# BBoard-JX2.net
KiCad netlist of a schematic drawn in Altium Designer
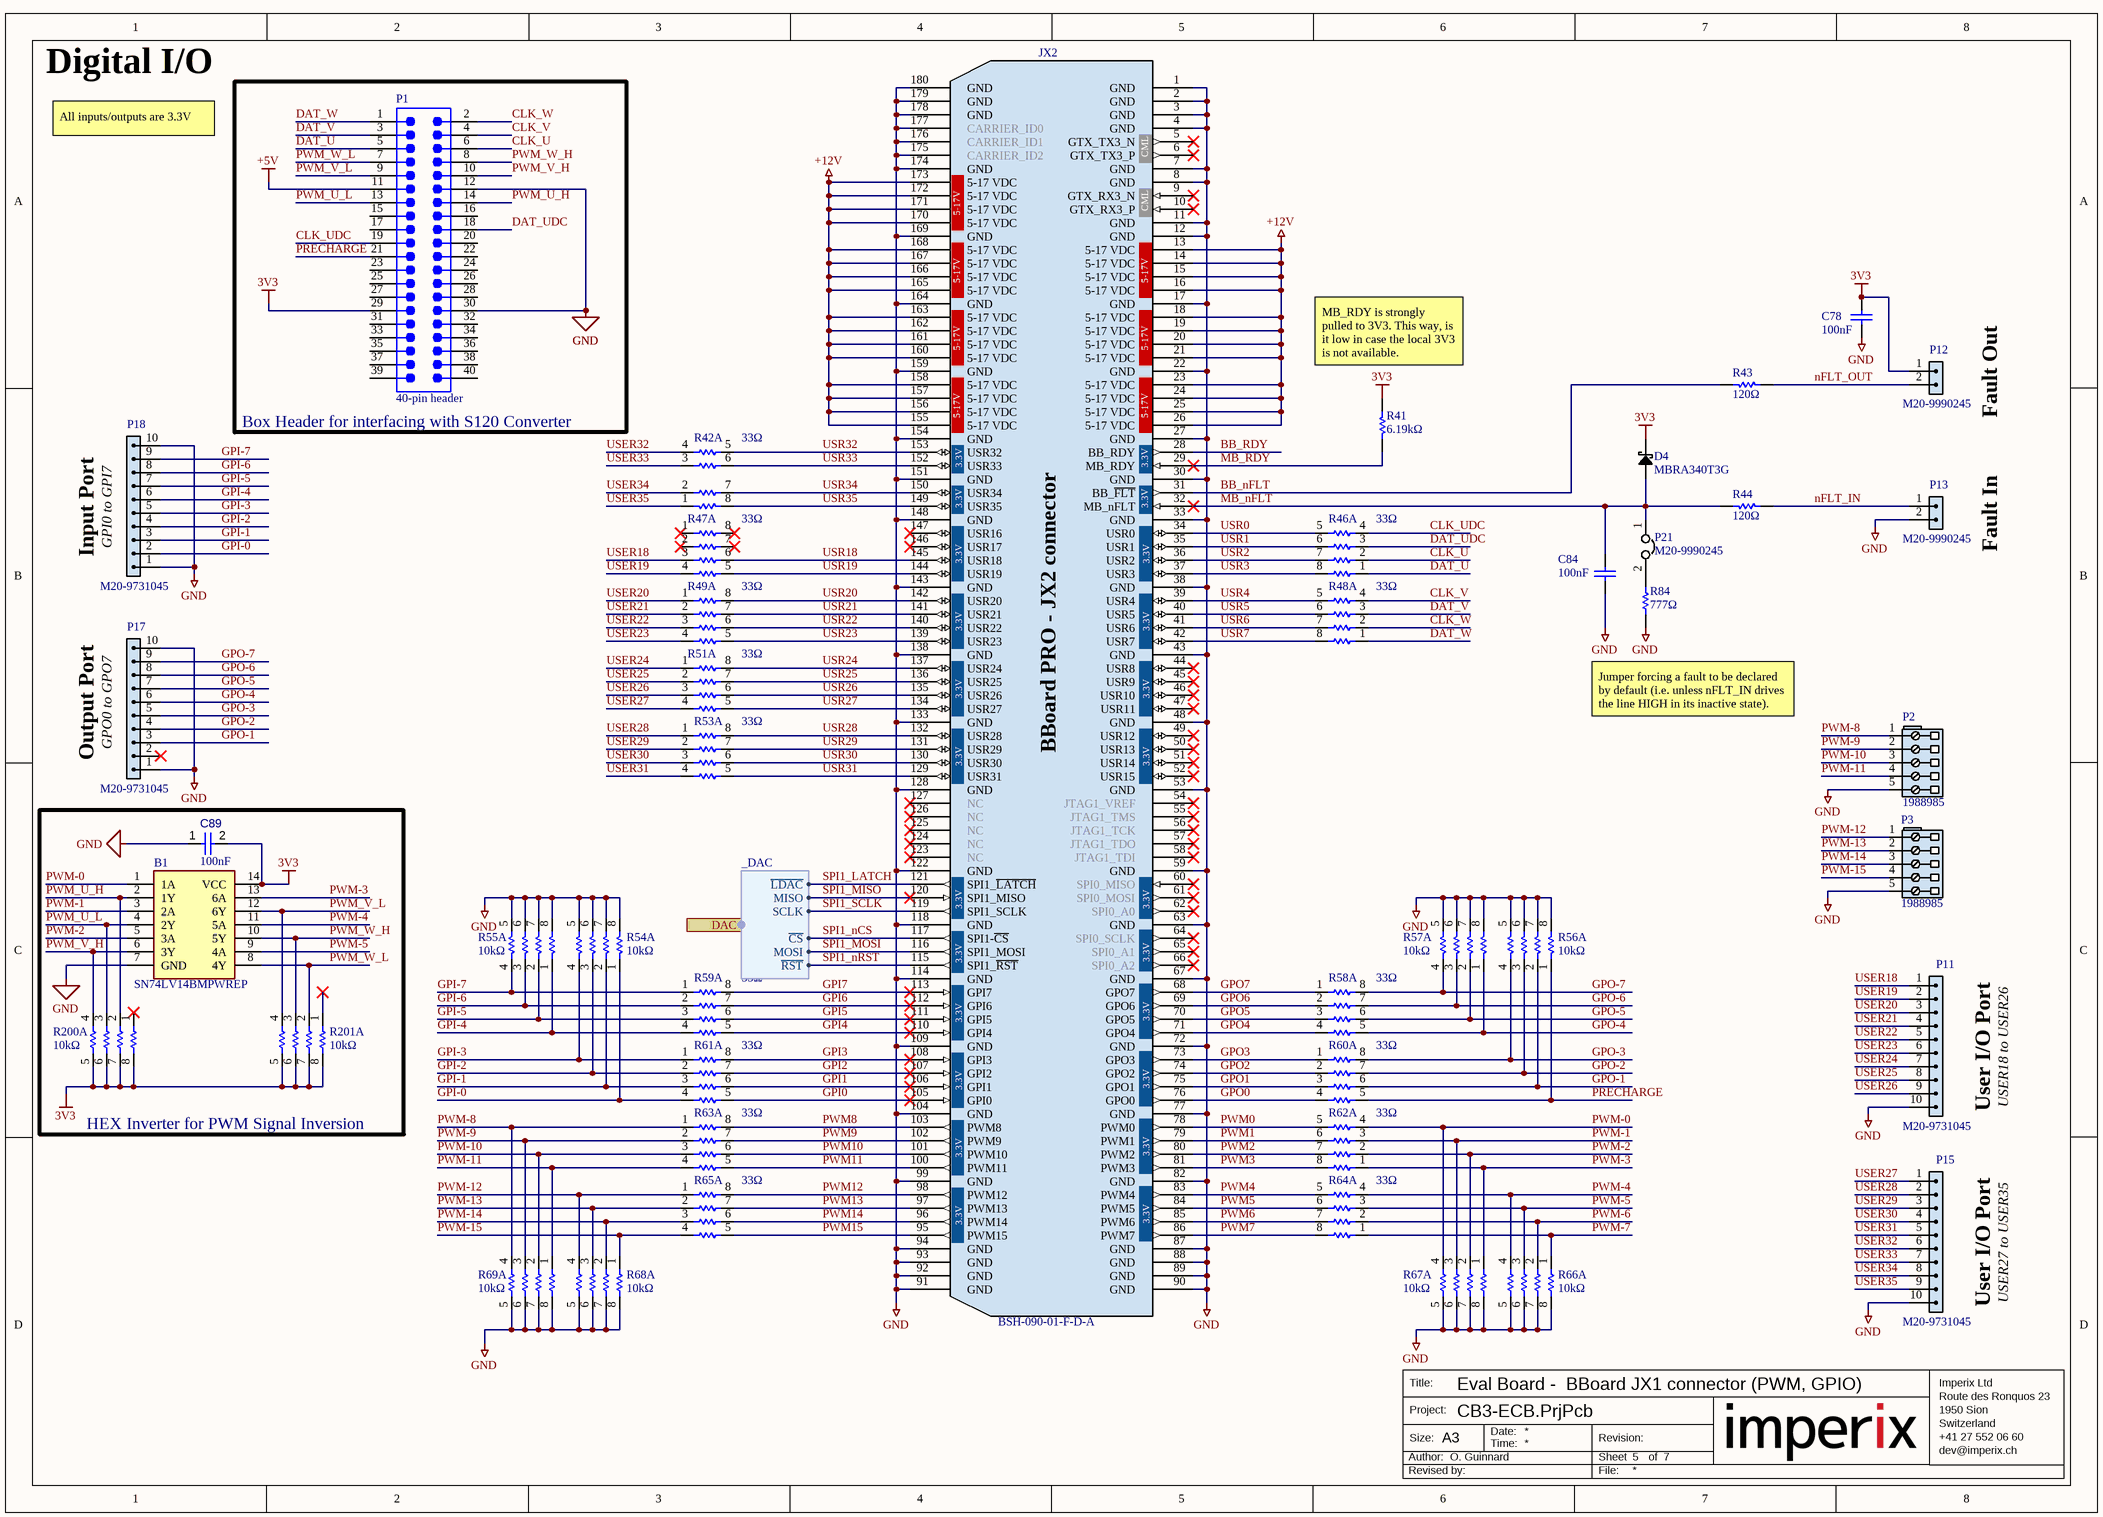
[diagram p0: BBoard-JX2.SchDoc]

(export (version "E")
  (design (tool "Eeschema 10.0.6"))
  (components
    (comp (ref "B1")
      (value "SN74LV14BMPWREP")
      (footprint "SOP65P640X120-14N")
      (fields (field (name "MOUSER PART NUMBER") "595-SN74LV14BMPWREP"))
      (libsource (lib "SN74LV14BMPWREP") (part "SN74LV14BMPWREP"))
    )
    (comp (ref "C78")
      (value "100nF")
      (footprint "CAPC1005L(0402)")
      (description "CAP CER 100NF 25V X7R 0402 10% (Generic Imperix Component)")
      (fields (field (name "TOLERANCE") "10%") (field (name "Comment") "CAP-100NF-25V-X7R-0402-10%"))
      (libsource (lib "CB3-ECB") (part "Capacitor non-polarized"))
    )
    (comp (ref "C84")
      (value "100nF")
      (footprint "CAPC1005L(0402)")
      (description "CAP CER 100NF 25V X7R 0402 10% (Generic Imperix Component)")
      (fields (field (name "TOLERANCE") "10%") (field (name "Comment") "CAP-100NF-25V-X7R-0402-10%"))
      (libsource (lib "CB3-ECB") (part "Capacitor non-polarized"))
    )
    (comp (ref "C89")
      (value "100nF")
      (footprint "CAPC0402(1005)60_L")
      (description "Chip Capacitor, 100nF +/-20%, 50V, 0402, Thickness 0.6 mm")
      (fields (field (name "TOLERANCE") "10%") (field (name "Comment") "Capacitor 100nF +/-20% 50V 0402"))
      (libsource (lib "Technische Universität Darmstadt -  Institut für Stromrichtertechnik und Antriebsregelung") (part "CAP-NP-2"))
    )
    (comp (ref "D4")
      (value "MBRA340T3G")
      (footprint "DO-214AC")
      (description "Diode Schottky 40 V 3A Surface Mount SMA")
      (libsource (lib "CB3-ECB") (part "Diode Schottky"))
    )
    (comp (ref "JX2")
      (value "BSH-090-01-F-D-A")
      (footprint "BSH-090-01-F-D-A")
      (description "JX2 for BBoard")
      (libsource (lib "CB3-ECB") (part "JX2 for Bboard"))
    )
    (comp (ref "P1")
      (value "40-pin header")
      (footprint "61204021621")
      (description "Würth WR-BHD Male Box Header")
      (fields (field (name "MANUFACTURER") "Würth") (field (name "MANUFACTURER PART NUMBER") "61204021621"))
      (libsource (lib "Altium Content Vault") (part "Header_Male_2R_40P"))
    )
    (comp (ref "P2")
      (value "1988985")
      (footprint "1988985")
      (description "Conn PC Terminal Block 5 POS 3.5mm Solder Thru-Hole 17.5A")
      (fields (field (name "VOLTAGE") "300V"))
      (libsource (lib "CB3-ECB") (part "1988985"))
    )
    (comp (ref "P3")
      (value "1988985")
      (footprint "1988985")
      (description "Conn PC Terminal Block 5 POS 3.5mm Solder Thru-Hole 17.5A")
      (fields (field (name "VOLTAGE") "300V"))
      (libsource (lib "CB3-ECB") (part "1988985"))
    )
    (comp (ref "P11")
      (value "M20-9731045")
      (footprint "M20-9731045")
      (description "Connector Header Through Hole 10 position 0.100\" (2.54mm)")
      (libsource (lib "") (part "Header 10-P_1"))
    )
    (comp (ref "P12")
      (value "M20-9990245")
      (footprint "M20-9990245")
      (description "Connector Header Through Hole 2 position 0.100\" (2.54mm)")
      (fields (field (name "VOLTAGE") "50V"))
      (libsource (lib "CB3-ECB") (part "M20-9990245"))
    )
    (comp (ref "P13")
      (value "M20-9990245")
      (footprint "M20-9990245")
      (description "Connector Header Through Hole 2 position 0.100\" (2.54mm)")
      (fields (field (name "VOLTAGE") "50V"))
      (libsource (lib "CB3-ECB") (part "M20-9990245"))
    )
    (comp (ref "P15")
      (value "M20-9731045")
      (footprint "M20-9731045")
      (description "Connector Header Through Hole 10 position 0.100\" (2.54mm)")
      (libsource (lib "") (part "Header 10-P_1"))
    )
    (comp (ref "P17")
      (value "M20-9731045")
      (footprint "M20-9731045")
      (description "Connector Header Through Hole 10 position 0.100\" (2.54mm)")
      (libsource (lib "CB3-ECB") (part "Header 10-P"))
    )
    (comp (ref "P18")
      (value "M20-9731045")
      (footprint "M20-9731045")
      (description "Connector Header Through Hole 10 position 0.100\" (2.54mm)")
      (libsource (lib "CB3-ECB") (part "Header 10-P"))
    )
    (comp (ref "P21")
      (value "M20-9990245")
      (footprint "M20-9990245")
      (description "Connector Header Through Hole 2 position 0.100\" (2.54mm)")
      (fields (field (name "VOLTAGE") "50V"))
      (libsource (lib "CB3-ECB") (part "Jumper 2-P"))
    )
    (comp (ref "R41")
      (value "6.19kΩ")
      (footprint "RESC1005L(0402)")
      (description "RES SMD 6.19KΩ 1/16W 100PPM 0402 1% (Generic Imperix Component)")
      (fields (field (name "TOLERANCE") "1%") (field (name "Comment") "RES-6.19KΩ-1/16W-100PPM-0402-1%"))
      (libsource (lib "CB3-ECB") (part "Resistor"))
    )
    (comp (ref "R42")
      (value "33Ω")
      (footprint "RESQUAD0804")
      (description "Res Thick Film Array 33 Ohm 5% ±200ppm/°C ISOL 8-Pin 0804(4 X 0402) Convex SMD Automotive T/R")
      (fields (field (name "TOLERANCE") "5%") (field (name "Comment") "EXB-28V330JX"))
      (libsource (lib "CB3-ECB") (part "Resistor Array Quad"))
    )
    (comp (ref "R43")
      (value "120Ω")
      (footprint "RESC1005L(0402)")
      (description "RES SMD 120Ω 1/16W 25PPM 0402 0.1% (Generic Imperix Component)")
      (fields (field (name "TOLERANCE") "0.1%") (field (name "Comment") "RES-120Ω-1/16W-25PPM-0402-0.1%"))
      (libsource (lib "CB3-ECB") (part "Resistor"))
    )
    (comp (ref "R44")
      (value "120Ω")
      (footprint "RESC1005L(0402)")
      (description "RES SMD 120Ω 1/16W 25PPM 0402 0.1% (Generic Imperix Component)")
      (fields (field (name "TOLERANCE") "0.1%") (field (name "Comment") "RES-120Ω-1/16W-25PPM-0402-0.1%"))
      (libsource (lib "CB3-ECB") (part "Resistor"))
    )
    (comp (ref "R46")
      (value "33Ω")
      (footprint "RESQUAD0804")
      (description "Res Thick Film Array 33 Ohm 5% ±200ppm/°C ISOL 8-Pin 0804(4 X 0402) Convex SMD Automotive T/R")
      (fields (field (name "TOLERANCE") "5%") (field (name "Comment") "EXB-28V330JX"))
      (libsource (lib "CB3-ECB") (part "Resistor Array Quad"))
    )
    (comp (ref "R47")
      (value "33Ω")
      (footprint "RESQUAD0804")
      (description "Res Thick Film Array 33 Ohm 5% ±200ppm/°C ISOL 8-Pin 0804(4 X 0402) Convex SMD Automotive T/R")
      (fields (field (name "TOLERANCE") "5%") (field (name "Comment") "EXB-28V330JX"))
      (libsource (lib "CB3-ECB") (part "Resistor Array Quad"))
    )
    (comp (ref "R48")
      (value "33Ω")
      (footprint "RESQUAD0804")
      (description "Res Thick Film Array 33 Ohm 5% ±200ppm/°C ISOL 8-Pin 0804(4 X 0402) Convex SMD Automotive T/R")
      (fields (field (name "TOLERANCE") "5%") (field (name "Comment") "EXB-28V330JX"))
      (libsource (lib "CB3-ECB") (part "Resistor Array Quad"))
    )
    (comp (ref "R49")
      (value "33Ω")
      (footprint "RESQUAD0804")
      (description "Res Thick Film Array 33 Ohm 5% ±200ppm/°C ISOL 8-Pin 0804(4 X 0402) Convex SMD Automotive T/R")
      (fields (field (name "TOLERANCE") "5%") (field (name "Comment") "EXB-28V330JX"))
      (libsource (lib "CB3-ECB") (part "Resistor Array Quad"))
    )
    (comp (ref "R51")
      (value "33Ω")
      (footprint "RESQUAD0804")
      (description "Res Thick Film Array 33 Ohm 5% ±200ppm/°C ISOL 8-Pin 0804(4 X 0402) Convex SMD Automotive T/R")
      (fields (field (name "TOLERANCE") "5%") (field (name "Comment") "EXB-28V330JX"))
      (libsource (lib "CB3-ECB") (part "Resistor Array Quad"))
    )
    (comp (ref "R53")
      (value "33Ω")
      (footprint "RESQUAD0804")
      (description "Res Thick Film Array 33 Ohm 5% ±200ppm/°C ISOL 8-Pin 0804(4 X 0402) Convex SMD Automotive T/R")
      (fields (field (name "TOLERANCE") "5%") (field (name "Comment") "EXB-28V330JX"))
      (libsource (lib "CB3-ECB") (part "Resistor Array Quad"))
    )
    (comp (ref "R54")
      (value "EXB-28V103JX")
      (footprint "RESQUAD0804")
      (description "Res Thick Film Array 10KΩ 5% ±200ppm/°C ISOL 8-Pin 0804(4 X 0402) Convex SMD Automotive T/R")
      (fields (field (name "TOLERANCE") "5%") (field (name "Comment") "EXB-28V103JX"))
      (libsource (lib "CB3-ECB") (part "Resistor Array Quad"))
    )
    (comp (ref "R55")
      (value "10kΩ")
      (footprint "RESQUAD0804")
      (description "Res Thick Film Array 10KΩ 5% ±200ppm/°C ISOL 8-Pin 0804(4 X 0402) Convex SMD Automotive T/R")
      (fields (field (name "TOLERANCE") "5%") (field (name "Comment") "EXB-28V103JX"))
      (libsource (lib "CB3-ECB") (part "Resistor Array Quad"))
    )
    (comp (ref "R56")
      (value "10kΩ")
      (footprint "RESQUAD0804")
      (description "Res Thick Film Array 10KΩ 5% ±200ppm/°C ISOL 8-Pin 0804(4 X 0402) Convex SMD Automotive T/R")
      (fields (field (name "TOLERANCE") "5%") (field (name "Comment") "EXB-28V103JX"))
      (libsource (lib "CB3-ECB") (part "Resistor Array Quad"))
    )
    (comp (ref "R57")
      (value "10kΩ")
      (footprint "RESQUAD0804")
      (description "Res Thick Film Array 10KΩ 5% ±200ppm/°C ISOL 8-Pin 0804(4 X 0402) Convex SMD Automotive T/R")
      (fields (field (name "TOLERANCE") "5%") (field (name "Comment") "EXB-28V103JX"))
      (libsource (lib "CB3-ECB") (part "Resistor Array Quad"))
    )
    (comp (ref "R58")
      (value "33Ω")
      (footprint "RESQUAD0804")
      (description "Res Thick Film Array 33 Ohm 5% ±200ppm/°C ISOL 8-Pin 0804(4 X 0402) Convex SMD Automotive T/R")
      (fields (field (name "TOLERANCE") "5%") (field (name "Comment") "EXB-28V330JX"))
      (libsource (lib "CB3-ECB") (part "Resistor Array Quad"))
    )
    (comp (ref "R59")
      (value "EXB-28V330JX")
      (footprint "RESQUAD0804")
      (description "Res Thick Film Array 33 Ohm 5% ±200ppm/°C ISOL 8-Pin 0804(4 X 0402) Convex SMD Automotive T/R")
      (fields (field (name "TOLERANCE") "5%") (field (name "Comment") "EXB-28V330JX"))
      (libsource (lib "CB3-ECB") (part "Resistor Array Quad"))
    )
    (comp (ref "R60")
      (value "33Ω")
      (footprint "RESQUAD0804")
      (description "Res Thick Film Array 33 Ohm 5% ±200ppm/°C ISOL 8-Pin 0804(4 X 0402) Convex SMD Automotive T/R")
      (fields (field (name "TOLERANCE") "5%") (field (name "Comment") "EXB-28V330JX"))
      (libsource (lib "CB3-ECB") (part "Resistor Array Quad"))
    )
    (comp (ref "R61")
      (value "EXB-28V330JX")
      (footprint "RESQUAD0804")
      (description "Res Thick Film Array 33 Ohm 5% ±200ppm/°C ISOL 8-Pin 0804(4 X 0402) Convex SMD Automotive T/R")
      (fields (field (name "TOLERANCE") "5%") (field (name "Comment") "EXB-28V330JX"))
      (libsource (lib "CB3-ECB") (part "Resistor Array Quad"))
    )
    (comp (ref "R62")
      (value "33Ω")
      (footprint "RESQUAD0804")
      (description "Res Thick Film Array 33 Ohm 5% ±200ppm/°C ISOL 8-Pin 0804(4 X 0402) Convex SMD Automotive T/R")
      (fields (field (name "TOLERANCE") "5%") (field (name "Comment") "EXB-28V330JX"))
      (libsource (lib "CB3-ECB") (part "Resistor Array Quad"))
    )
    (comp (ref "R63")
      (value "33Ω")
      (footprint "RESQUAD0804")
      (description "Res Thick Film Array 33 Ohm 5% ±200ppm/°C ISOL 8-Pin 0804(4 X 0402) Convex SMD Automotive T/R")
      (fields (field (name "TOLERANCE") "5%") (field (name "Comment") "EXB-28V330JX"))
      (libsource (lib "CB3-ECB") (part "Resistor Array Quad"))
    )
    (comp (ref "R64")
      (value "EXB-28V330JX")
      (footprint "RESQUAD0804")
      (description "Res Thick Film Array 33 Ohm 5% ±200ppm/°C ISOL 8-Pin 0804(4 X 0402) Convex SMD Automotive T/R")
      (fields (field (name "TOLERANCE") "5%") (field (name "Comment") "EXB-28V330JX"))
      (libsource (lib "CB3-ECB") (part "Resistor Array Quad"))
    )
    (comp (ref "R65")
      (value "EXB-28V330JX")
      (footprint "RESQUAD0804")
      (description "Res Thick Film Array 33 Ohm 5% ±200ppm/°C ISOL 8-Pin 0804(4 X 0402) Convex SMD Automotive T/R")
      (fields (field (name "TOLERANCE") "5%") (field (name "Comment") "EXB-28V330JX"))
      (libsource (lib "CB3-ECB") (part "Resistor Array Quad"))
    )
    (comp (ref "R66")
      (value "10kΩ")
      (footprint "RESQUAD0804")
      (description "Res Thick Film Array 10KΩ 5% ±200ppm/°C ISOL 8-Pin 0804(4 X 0402) Convex SMD Automotive T/R")
      (fields (field (name "TOLERANCE") "5%") (field (name "Comment") "EXB-28V103JX"))
      (libsource (lib "CB3-ECB") (part "Resistor Array Quad"))
    )
    (comp (ref "R67")
      (value "10kΩ")
      (footprint "RESQUAD0804")
      (description "Res Thick Film Array 10KΩ 5% ±200ppm/°C ISOL 8-Pin 0804(4 X 0402) Convex SMD Automotive T/R")
      (fields (field (name "TOLERANCE") "5%") (field (name "Comment") "EXB-28V103JX"))
      (libsource (lib "CB3-ECB") (part "Resistor Array Quad"))
    )
    (comp (ref "R68")
      (value "EXB-28V103JX")
      (footprint "RESQUAD0804")
      (description "Res Thick Film Array 10KΩ 5% ±200ppm/°C ISOL 8-Pin 0804(4 X 0402) Convex SMD Automotive T/R")
      (fields (field (name "TOLERANCE") "5%") (field (name "Comment") "EXB-28V103JX"))
      (libsource (lib "CB3-ECB") (part "Resistor Array Quad"))
    )
    (comp (ref "R69")
      (value "10kΩ")
      (footprint "RESQUAD0804")
      (description "Res Thick Film Array 10KΩ 5% ±200ppm/°C ISOL 8-Pin 0804(4 X 0402) Convex SMD Automotive T/R")
      (fields (field (name "TOLERANCE") "5%") (field (name "Comment") "EXB-28V103JX"))
      (libsource (lib "CB3-ECB") (part "Resistor Array Quad"))
    )
    (comp (ref "R84")
      (value "777Ω")
      (footprint "RESC1005L(0402)")
      (description "RES SMD 777Ω 1/16W 25PPM 0402 0.1% (Generic Imperix Component)")
      (fields (field (name "TOLERANCE") "0.1%") (field (name "Comment") "RES-777Ω-1/16W-25PPM-0402-0.1%"))
      (libsource (lib "CB3-ECB") (part "Resistor"))
    )
    (comp (ref "R200")
      (value "10kΩ")
      (footprint "RESQUAD0804")
      (description "Res Thick Film Array 10KΩ 5% ±200ppm/°C ISOL 8-Pin 0804(4 X 0402) Convex SMD Automotive T/R")
      (fields (field (name "TOLERANCE") "5%") (field (name "Comment") "EXB-28V103JX"))
      (libsource (lib "CB3-ECB") (part "Resistor Array Quad"))
    )
    (comp (ref "R201")
      (value "10kΩ")
      (footprint "RESQUAD0804")
      (description "Res Thick Film Array 10KΩ 5% ±200ppm/°C ISOL 8-Pin 0804(4 X 0402) Convex SMD Automotive T/R")
      (fields (field (name "TOLERANCE") "5%") (field (name "Comment") "EXB-28V103JX"))
      (libsource (lib "CB3-ECB") (part "Resistor Array Quad"))
    )
  )
  (nets
    (net (code "2") (name "+5V") (class "Default")
      (node (ref "P1") (pin "11") (pinfunction "11_11") (pintype "passive"))
    )
    (net (code "3") (name "+12V") (class "Default")
      (node (ref "JX2") (pin "13") (pinfunction "5-17_VDC_13") (pintype "power_in"))
      (node (ref "JX2") (pin "14") (pinfunction "5-17_VDC_14") (pintype "power_in"))
      (node (ref "JX2") (pin "15") (pinfunction "5-17_VDC_15") (pintype "power_in"))
      (node (ref "JX2") (pin "155") (pinfunction "5-17_VDC_155") (pintype "power_in"))
      (node (ref "JX2") (pin "156") (pinfunction "5-17_VDC_156") (pintype "power_in"))
      (node (ref "JX2") (pin "157") (pinfunction "5-17_VDC_157") (pintype "power_in"))
      (node (ref "JX2") (pin "158") (pinfunction "5-17_VDC_158") (pintype "power_in"))
      (node (ref "JX2") (pin "16") (pinfunction "5-17_VDC_16") (pintype "power_in"))
      (node (ref "JX2") (pin "160") (pinfunction "5-17_VDC_160") (pintype "power_in"))
      (node (ref "JX2") (pin "161") (pinfunction "5-17_VDC_161") (pintype "power_in"))
      (node (ref "JX2") (pin "162") (pinfunction "5-17_VDC_162") (pintype "power_in"))
      (node (ref "JX2") (pin "163") (pinfunction "5-17_VDC_163") (pintype "power_in"))
      (node (ref "JX2") (pin "165") (pinfunction "5-17_VDC_165") (pintype "power_in"))
      (node (ref "JX2") (pin "166") (pinfunction "5-17_VDC_166") (pintype "power_in"))
      (node (ref "JX2") (pin "167") (pinfunction "5-17_VDC_167") (pintype "power_in"))
      (node (ref "JX2") (pin "168") (pinfunction "5-17_VDC_168") (pintype "power_in"))
      (node (ref "JX2") (pin "170") (pinfunction "5-17_VDC_170") (pintype "power_in"))
      (node (ref "JX2") (pin "171") (pinfunction "5-17_VDC_171") (pintype "power_in"))
      (node (ref "JX2") (pin "172") (pinfunction "5-17_VDC_172") (pintype "power_in"))
      (node (ref "JX2") (pin "173") (pinfunction "5-17_VDC_173") (pintype "power_in"))
      (node (ref "JX2") (pin "18") (pinfunction "5-17_VDC_18") (pintype "power_in"))
      (node (ref "JX2") (pin "19") (pinfunction "5-17_VDC_19") (pintype "power_in"))
      (node (ref "JX2") (pin "20") (pinfunction "5-17_VDC_20") (pintype "power_in"))
      (node (ref "JX2") (pin "21") (pinfunction "5-17_VDC_21") (pintype "power_in"))
      (node (ref "JX2") (pin "23") (pinfunction "5-17_VDC_23") (pintype "power_in"))
      (node (ref "JX2") (pin "24") (pinfunction "5-17_VDC_24") (pintype "power_in"))
      (node (ref "JX2") (pin "25") (pinfunction "5-17_VDC_25") (pintype "power_in"))
      (node (ref "JX2") (pin "26") (pinfunction "5-17_VDC_26") (pintype "power_in"))
    )
    (net (code "4") (name "/BB_RDY") (class "Default")
      (node (ref "JX2") (pin "28") (pinfunction "BB_RDY_28") (pintype "output"))
    )
    (net (code "5") (name "/BB_nFLT") (class "Default")
      (node (ref "JX2") (pin "31") (pinfunction "BB_~{FLT}_31") (pintype "output"))
      (node (ref "R43") (pin "1") (pinfunction "1_1") (pintype "passive"))
    )
    (net (code "6") (name "/CLK_U") (class "Default")
      (node (ref "P1") (pin "6") (pinfunction "6_6") (pintype "passive"))
      (node (ref "R46") (pin "2") (pinfunction "2_2") (pintype "passive"))
    )
    (net (code "7") (name "/CLK_UDC") (class "Default")
      (node (ref "P1") (pin "19") (pinfunction "19_19") (pintype "passive"))
      (node (ref "R46") (pin "4") (pinfunction "4_4") (pintype "passive"))
    )
    (net (code "8") (name "/CLK_V") (class "Default")
      (node (ref "P1") (pin "4") (pinfunction "4_4") (pintype "passive"))
      (node (ref "R48") (pin "4") (pinfunction "4_4") (pintype "passive"))
    )
    (net (code "9") (name "/CLK_W") (class "Default")
      (node (ref "P1") (pin "2") (pinfunction "2_2") (pintype "passive"))
      (node (ref "R48") (pin "2") (pinfunction "2_2") (pintype "passive"))
    )
    (net (code "10") (name "/DAT_U") (class "Default")
      (node (ref "P1") (pin "5") (pinfunction "5_5") (pintype "passive"))
      (node (ref "R46") (pin "1") (pinfunction "1_1") (pintype "passive"))
    )
    (net (code "11") (name "/DAT_UDC") (class "Default")
      (node (ref "P1") (pin "18") (pinfunction "18_18") (pintype "passive"))
      (node (ref "R46") (pin "3") (pinfunction "3_3") (pintype "passive"))
    )
    (net (code "12") (name "/DAT_V") (class "Default")
      (node (ref "P1") (pin "3") (pinfunction "3_3") (pintype "passive"))
      (node (ref "R48") (pin "3") (pinfunction "3_3") (pintype "passive"))
    )
    (net (code "13") (name "/DAT_W") (class "Default")
      (node (ref "P1") (pin "1") (pinfunction "1_1") (pintype "passive"))
      (node (ref "R48") (pin "1") (pinfunction "1_1") (pintype "passive"))
    )
    (net (code "14") (name "/GPI-0") (class "Default")
      (node (ref "P18") (pin "2") (pinfunction "2_2") (pintype "passive"))
      (node (ref "R54") (pin "1") (pinfunction "1_1") (pintype "passive"))
      (node (ref "R61") (pin "4") (pinfunction "4_4") (pintype "passive"))
    )
    (net (code "15") (name "/GPI-1") (class "Default")
      (node (ref "P18") (pin "3") (pinfunction "3_3") (pintype "passive"))
      (node (ref "R54") (pin "2") (pinfunction "2_2") (pintype "passive"))
      (node (ref "R61") (pin "3") (pinfunction "3_3") (pintype "passive"))
    )
    (net (code "16") (name "/GPI-2") (class "Default")
      (node (ref "P18") (pin "4") (pinfunction "4_4") (pintype "passive"))
      (node (ref "R54") (pin "3") (pinfunction "3_3") (pintype "passive"))
      (node (ref "R61") (pin "2") (pinfunction "2_2") (pintype "passive"))
    )
    (net (code "17") (name "/GPI-3") (class "Default")
      (node (ref "P18") (pin "5") (pinfunction "5_5") (pintype "passive"))
      (node (ref "R54") (pin "4") (pinfunction "4_4") (pintype "passive"))
      (node (ref "R61") (pin "1") (pinfunction "1_1") (pintype "passive"))
    )
    (net (code "18") (name "/GPI-4") (class "Default")
      (node (ref "P18") (pin "6") (pinfunction "6_6") (pintype "passive"))
      (node (ref "R55") (pin "1") (pinfunction "1_1") (pintype "passive"))
      (node (ref "R59") (pin "4") (pinfunction "4_4") (pintype "passive"))
    )
    (net (code "19") (name "/GPI-5") (class "Default")
      (node (ref "P18") (pin "7") (pinfunction "7_7") (pintype "passive"))
      (node (ref "R55") (pin "2") (pinfunction "2_2") (pintype "passive"))
      (node (ref "R59") (pin "3") (pinfunction "3_3") (pintype "passive"))
    )
    (net (code "20") (name "/GPI-6") (class "Default")
      (node (ref "P18") (pin "8") (pinfunction "8_8") (pintype "passive"))
      (node (ref "R55") (pin "3") (pinfunction "3_3") (pintype "passive"))
      (node (ref "R59") (pin "2") (pinfunction "2_2") (pintype "passive"))
    )
    (net (code "21") (name "/GPI-7") (class "Default")
      (node (ref "P18") (pin "9") (pinfunction "9_9") (pintype "passive"))
      (node (ref "R55") (pin "4") (pinfunction "4_4") (pintype "passive"))
      (node (ref "R59") (pin "1") (pinfunction "1_1") (pintype "passive"))
    )
    (net (code "22") (name "/GPI0") (class "Default")
      (node (ref "JX2") (pin "105") (pinfunction "GPI0_105") (pintype "input"))
      (node (ref "R61") (pin "5") (pinfunction "5_5") (pintype "passive"))
    )
    (net (code "23") (name "/GPI1") (class "Default")
      (node (ref "JX2") (pin "106") (pinfunction "GPI1_106") (pintype "input"))
      (node (ref "R61") (pin "6") (pinfunction "6_6") (pintype "passive"))
    )
    (net (code "24") (name "/GPI2") (class "Default")
      (node (ref "JX2") (pin "107") (pinfunction "GPI2_107") (pintype "input"))
      (node (ref "R61") (pin "7") (pinfunction "7_7") (pintype "passive"))
    )
    (net (code "25") (name "/GPI3") (class "Default")
      (node (ref "JX2") (pin "108") (pinfunction "GPI3_108") (pintype "input"))
      (node (ref "R61") (pin "8") (pinfunction "8_8") (pintype "passive"))
    )
    (net (code "26") (name "/GPI4") (class "Default")
      (node (ref "JX2") (pin "110") (pinfunction "GPI4_110") (pintype "input"))
      (node (ref "R59") (pin "5") (pinfunction "5_5") (pintype "passive"))
    )
    (net (code "27") (name "/GPI5") (class "Default")
      (node (ref "JX2") (pin "111") (pinfunction "GPI5_111") (pintype "input"))
      (node (ref "R59") (pin "6") (pinfunction "6_6") (pintype "passive"))
    )
    (net (code "28") (name "/GPI6") (class "Default")
      (node (ref "JX2") (pin "112") (pinfunction "GPI6_112") (pintype "input"))
      (node (ref "R59") (pin "7") (pinfunction "7_7") (pintype "passive"))
    )
    (net (code "29") (name "/GPI7") (class "Default")
      (node (ref "JX2") (pin "113") (pinfunction "GPI7_113") (pintype "input"))
      (node (ref "R59") (pin "8") (pinfunction "8_8") (pintype "passive"))
    )
    (net (code "30") (name "/GPO-1") (class "Default")
      (node (ref "P17") (pin "3") (pinfunction "3_3") (pintype "passive"))
      (node (ref "R56") (pin "2") (pinfunction "2_2") (pintype "passive"))
      (node (ref "R60") (pin "6") (pinfunction "6_6") (pintype "passive"))
    )
    (net (code "31") (name "/GPO-2") (class "Default")
      (node (ref "P17") (pin "4") (pinfunction "4_4") (pintype "passive"))
      (node (ref "R56") (pin "3") (pinfunction "3_3") (pintype "passive"))
      (node (ref "R60") (pin "7") (pinfunction "7_7") (pintype "passive"))
    )
    (net (code "32") (name "/GPO-3") (class "Default")
      (node (ref "P17") (pin "5") (pinfunction "5_5") (pintype "passive"))
      (node (ref "R56") (pin "4") (pinfunction "4_4") (pintype "passive"))
      (node (ref "R60") (pin "8") (pinfunction "8_8") (pintype "passive"))
    )
    (net (code "33") (name "/GPO-4") (class "Default")
      (node (ref "P17") (pin "6") (pinfunction "6_6") (pintype "passive"))
      (node (ref "R57") (pin "1") (pinfunction "1_1") (pintype "passive"))
      (node (ref "R58") (pin "5") (pinfunction "5_5") (pintype "passive"))
    )
    (net (code "34") (name "/GPO-5") (class "Default")
      (node (ref "P17") (pin "7") (pinfunction "7_7") (pintype "passive"))
      (node (ref "R57") (pin "2") (pinfunction "2_2") (pintype "passive"))
      (node (ref "R58") (pin "6") (pinfunction "6_6") (pintype "passive"))
    )
    (net (code "35") (name "/GPO-6") (class "Default")
      (node (ref "P17") (pin "8") (pinfunction "8_8") (pintype "passive"))
      (node (ref "R57") (pin "3") (pinfunction "3_3") (pintype "passive"))
      (node (ref "R58") (pin "7") (pinfunction "7_7") (pintype "passive"))
    )
    (net (code "36") (name "/GPO-7") (class "Default")
      (node (ref "P17") (pin "9") (pinfunction "9_9") (pintype "passive"))
      (node (ref "R57") (pin "4") (pinfunction "4_4") (pintype "passive"))
      (node (ref "R58") (pin "8") (pinfunction "8_8") (pintype "passive"))
    )
    (net (code "37") (name "/GPO0") (class "Default")
      (node (ref "JX2") (pin "76") (pinfunction "GPO0_76") (pintype "output"))
      (node (ref "R60") (pin "4") (pinfunction "4_4") (pintype "passive"))
    )
    (net (code "38") (name "/GPO1") (class "Default")
      (node (ref "JX2") (pin "75") (pinfunction "GPO1_75") (pintype "output"))
      (node (ref "R60") (pin "3") (pinfunction "3_3") (pintype "passive"))
    )
    (net (code "39") (name "/GPO2") (class "Default")
      (node (ref "JX2") (pin "74") (pinfunction "GPO2_74") (pintype "output"))
      (node (ref "R60") (pin "2") (pinfunction "2_2") (pintype "passive"))
    )
    (net (code "40") (name "/GPO3") (class "Default")
      (node (ref "JX2") (pin "73") (pinfunction "GPO3_73") (pintype "output"))
      (node (ref "R60") (pin "1") (pinfunction "1_1") (pintype "passive"))
    )
    (net (code "41") (name "/GPO4") (class "Default")
      (node (ref "JX2") (pin "71") (pinfunction "GPO4_71") (pintype "output"))
      (node (ref "R58") (pin "4") (pinfunction "4_4") (pintype "passive"))
    )
    (net (code "42") (name "/GPO5") (class "Default")
      (node (ref "JX2") (pin "70") (pinfunction "GPO5_70") (pintype "output"))
      (node (ref "R58") (pin "3") (pinfunction "3_3") (pintype "passive"))
    )
    (net (code "43") (name "/GPO6") (class "Default")
      (node (ref "JX2") (pin "69") (pinfunction "GPO6_69") (pintype "output"))
      (node (ref "R58") (pin "2") (pinfunction "2_2") (pintype "passive"))
    )
    (net (code "44") (name "/GPO7") (class "Default")
      (node (ref "JX2") (pin "68") (pinfunction "GPO7_68") (pintype "output"))
      (node (ref "R58") (pin "1") (pinfunction "1_1") (pintype "passive"))
    )
    (net (code "45") (name "/MB_RDY") (class "Default")
      (node (ref "JX2") (pin "29") (pinfunction "MB_RDY_29") (pintype "input"))
      (node (ref "R41") (pin "2") (pinfunction "2_2") (pintype "passive"))
    )
    (net (code "46") (name "/MB_nFLT") (class "Default")
      (node (ref "C84") (pin "2") (pinfunction "2_2") (pintype "passive"))
      (node (ref "D4") (pin "A") (pinfunction "A_A") (pintype "passive"))
      (node (ref "JX2") (pin "32") (pinfunction "MB_nFLT_32") (pintype "input"))
      (node (ref "P21") (pin "1") (pinfunction "1_1") (pintype "passive"))
      (node (ref "R44") (pin "1") (pinfunction "1_1") (pintype "passive"))
    )
    (net (code "47") (name "/PRECHARGE") (class "Default")
      (node (ref "P1") (pin "21") (pinfunction "21_21") (pintype "passive"))
      (node (ref "R56") (pin "1") (pinfunction "1_1") (pintype "passive"))
      (node (ref "R60") (pin "5") (pinfunction "5_5") (pintype "passive"))
    )
    (net (code "48") (name "/PWM-0") (class "Default")
      (node (ref "B1") (pin "1") (pinfunction "1A_1") (pintype "passive"))
      (node (ref "R62") (pin "4") (pinfunction "4_4") (pintype "passive"))
      (node (ref "R67") (pin "4") (pinfunction "4_4") (pintype "passive"))
    )
    (net (code "49") (name "/PWM-1") (class "Default")
      (node (ref "B1") (pin "3") (pinfunction "2A_3") (pintype "passive"))
      (node (ref "R62") (pin "3") (pinfunction "3_3") (pintype "passive"))
      (node (ref "R67") (pin "3") (pinfunction "3_3") (pintype "passive"))
    )
    (net (code "50") (name "/PWM-2") (class "Default")
      (node (ref "B1") (pin "5") (pinfunction "3A_5") (pintype "passive"))
      (node (ref "R62") (pin "2") (pinfunction "2_2") (pintype "passive"))
      (node (ref "R67") (pin "2") (pinfunction "2_2") (pintype "passive"))
    )
    (net (code "51") (name "/PWM-3") (class "Default")
      (node (ref "B1") (pin "13") (pinfunction "6A_13") (pintype "passive"))
      (node (ref "R62") (pin "1") (pinfunction "1_1") (pintype "passive"))
      (node (ref "R67") (pin "1") (pinfunction "1_1") (pintype "passive"))
    )
    (net (code "52") (name "/PWM-4") (class "Default")
      (node (ref "B1") (pin "11") (pinfunction "5A_11") (pintype "passive"))
      (node (ref "R64") (pin "4") (pinfunction "4_4") (pintype "passive"))
      (node (ref "R66") (pin "4") (pinfunction "4_4") (pintype "passive"))
    )
    (net (code "53") (name "/PWM-5") (class "Default")
      (node (ref "B1") (pin "9") (pinfunction "4A_9") (pintype "passive"))
      (node (ref "R64") (pin "3") (pinfunction "3_3") (pintype "passive"))
      (node (ref "R66") (pin "3") (pinfunction "3_3") (pintype "passive"))
    )
    (net (code "54") (name "/PWM-6") (class "Default")
      (node (ref "R64") (pin "2") (pinfunction "2_2") (pintype "passive"))
      (node (ref "R66") (pin "2") (pinfunction "2_2") (pintype "passive"))
    )
    (net (code "55") (name "/PWM-7") (class "Default")
      (node (ref "R64") (pin "1") (pinfunction "1_1") (pintype "passive"))
      (node (ref "R66") (pin "1") (pinfunction "1_1") (pintype "passive"))
    )
    (net (code "56") (name "/PWM-8") (class "Default")
      (node (ref "P2") (pin "1") (pinfunction "1_1") (pintype "passive"))
      (node (ref "R63") (pin "1") (pinfunction "1_1") (pintype "passive"))
      (node (ref "R69") (pin "4") (pinfunction "4_4") (pintype "passive"))
    )
    (net (code "57") (name "/PWM-9") (class "Default")
      (node (ref "P2") (pin "2") (pinfunction "2_2") (pintype "passive"))
      (node (ref "R63") (pin "2") (pinfunction "2_2") (pintype "passive"))
      (node (ref "R69") (pin "3") (pinfunction "3_3") (pintype "passive"))
    )
    (net (code "58") (name "/PWM-10") (class "Default")
      (node (ref "P2") (pin "3") (pinfunction "3_3") (pintype "passive"))
      (node (ref "R63") (pin "3") (pinfunction "3_3") (pintype "passive"))
      (node (ref "R69") (pin "2") (pinfunction "2_2") (pintype "passive"))
    )
    (net (code "59") (name "/PWM-11") (class "Default")
      (node (ref "P2") (pin "4") (pinfunction "4_4") (pintype "passive"))
      (node (ref "R63") (pin "4") (pinfunction "4_4") (pintype "passive"))
      (node (ref "R69") (pin "1") (pinfunction "1_1") (pintype "passive"))
    )
    (net (code "60") (name "/PWM-12") (class "Default")
      (node (ref "P3") (pin "1") (pinfunction "1_1") (pintype "passive"))
      (node (ref "R65") (pin "1") (pinfunction "1_1") (pintype "passive"))
      (node (ref "R68") (pin "4") (pinfunction "4_4") (pintype "passive"))
    )
    (net (code "61") (name "/PWM-13") (class "Default")
      (node (ref "P3") (pin "2") (pinfunction "2_2") (pintype "passive"))
      (node (ref "R65") (pin "2") (pinfunction "2_2") (pintype "passive"))
      (node (ref "R68") (pin "3") (pinfunction "3_3") (pintype "passive"))
    )
    (net (code "62") (name "/PWM-14") (class "Default")
      (node (ref "P3") (pin "3") (pinfunction "3_3") (pintype "passive"))
      (node (ref "R65") (pin "3") (pinfunction "3_3") (pintype "passive"))
      (node (ref "R68") (pin "2") (pinfunction "2_2") (pintype "passive"))
    )
    (net (code "63") (name "/PWM-15") (class "Default")
      (node (ref "P3") (pin "4") (pinfunction "4_4") (pintype "passive"))
      (node (ref "R65") (pin "4") (pinfunction "4_4") (pintype "passive"))
      (node (ref "R68") (pin "1") (pinfunction "1_1") (pintype "passive"))
    )
    (net (code "64") (name "/PWM0") (class "Default")
      (node (ref "JX2") (pin "78") (pinfunction "PWM0_78") (pintype "output"))
      (node (ref "R62") (pin "5") (pinfunction "5_5") (pintype "passive"))
    )
    (net (code "65") (name "/PWM1") (class "Default")
      (node (ref "JX2") (pin "79") (pinfunction "PWM1_79") (pintype "output"))
      (node (ref "R62") (pin "6") (pinfunction "6_6") (pintype "passive"))
    )
    (net (code "66") (name "/PWM2") (class "Default")
      (node (ref "JX2") (pin "80") (pinfunction "PWM2_80") (pintype "output"))
      (node (ref "R62") (pin "7") (pinfunction "7_7") (pintype "passive"))
    )
    (net (code "67") (name "/PWM3") (class "Default")
      (node (ref "JX2") (pin "81") (pinfunction "PWM3_81") (pintype "output"))
      (node (ref "R62") (pin "8") (pinfunction "8_8") (pintype "passive"))
    )
    (net (code "68") (name "/PWM4") (class "Default")
      (node (ref "JX2") (pin "83") (pinfunction "PWM4_83") (pintype "output"))
      (node (ref "R64") (pin "5") (pinfunction "5_5") (pintype "passive"))
    )
    (net (code "69") (name "/PWM5") (class "Default")
      (node (ref "JX2") (pin "84") (pinfunction "PWM5_84") (pintype "output"))
      (node (ref "R64") (pin "6") (pinfunction "6_6") (pintype "passive"))
    )
    (net (code "70") (name "/PWM6") (class "Default")
      (node (ref "JX2") (pin "85") (pinfunction "PWM6_85") (pintype "output"))
      (node (ref "R64") (pin "7") (pinfunction "7_7") (pintype "passive"))
    )
    (net (code "71") (name "/PWM7") (class "Default")
      (node (ref "JX2") (pin "86") (pinfunction "PWM7_86") (pintype "output"))
      (node (ref "R64") (pin "8") (pinfunction "8_8") (pintype "passive"))
    )
    (net (code "72") (name "/PWM8") (class "Default")
      (node (ref "JX2") (pin "103") (pinfunction "PWM8_103") (pintype "output"))
      (node (ref "R63") (pin "8") (pinfunction "8_8") (pintype "passive"))
    )
    (net (code "73") (name "/PWM9") (class "Default")
      (node (ref "JX2") (pin "102") (pinfunction "PWM9_102") (pintype "output"))
      (node (ref "R63") (pin "7") (pinfunction "7_7") (pintype "passive"))
    )
    (net (code "74") (name "/PWM10") (class "Default")
      (node (ref "JX2") (pin "101") (pinfunction "PWM10_101") (pintype "output"))
      (node (ref "R63") (pin "6") (pinfunction "6_6") (pintype "passive"))
    )
    (net (code "75") (name "/PWM11") (class "Default")
      (node (ref "JX2") (pin "100") (pinfunction "PWM11_100") (pintype "output"))
      (node (ref "R63") (pin "5") (pinfunction "5_5") (pintype "passive"))
    )
    (net (code "76") (name "/PWM12") (class "Default")
      (node (ref "JX2") (pin "98") (pinfunction "PWM12_98") (pintype "output"))
      (node (ref "R65") (pin "8") (pinfunction "8_8") (pintype "passive"))
    )
    (net (code "77") (name "/PWM13") (class "Default")
      (node (ref "JX2") (pin "97") (pinfunction "PWM13_97") (pintype "output"))
      (node (ref "R65") (pin "7") (pinfunction "7_7") (pintype "passive"))
    )
    (net (code "78") (name "/PWM14") (class "Default")
      (node (ref "JX2") (pin "96") (pinfunction "PWM14_96") (pintype "output"))
      (node (ref "R65") (pin "6") (pinfunction "6_6") (pintype "passive"))
    )
    (net (code "79") (name "/PWM15") (class "Default")
      (node (ref "JX2") (pin "95") (pinfunction "PWM15_95") (pintype "output"))
      (node (ref "R65") (pin "5") (pinfunction "5_5") (pintype "passive"))
    )
    (net (code "80") (name "/PWM_U_H") (class "Default")
      (node (ref "B1") (pin "2") (pinfunction "1Y_2") (pintype "passive"))
      (node (ref "P1") (pin "14") (pinfunction "14_14") (pintype "passive"))
      (node (ref "R200") (pin "2") (pinfunction "2_2") (pintype "passive"))
    )
    (net (code "81") (name "/PWM_U_L") (class "Default")
      (node (ref "B1") (pin "4") (pinfunction "2Y_4") (pintype "passive"))
      (node (ref "P1") (pin "13") (pinfunction "13_13") (pintype "passive"))
      (node (ref "R200") (pin "3") (pinfunction "3_3") (pintype "passive"))
    )
    (net (code "82") (name "/PWM_V_H") (class "Default")
      (node (ref "B1") (pin "6") (pinfunction "3Y_6") (pintype "passive"))
      (node (ref "P1") (pin "10") (pinfunction "10_10") (pintype "passive"))
      (node (ref "R200") (pin "4") (pinfunction "4_4") (pintype "passive"))
    )
    (net (code "83") (name "/PWM_V_L") (class "Default")
      (node (ref "B1") (pin "12") (pinfunction "6Y_12") (pintype "passive"))
      (node (ref "P1") (pin "9") (pinfunction "9_9") (pintype "passive"))
      (node (ref "R201") (pin "4") (pinfunction "4_4") (pintype "passive"))
    )
    (net (code "84") (name "/PWM_W_H") (class "Default")
      (node (ref "B1") (pin "10") (pinfunction "5Y_10") (pintype "passive"))
      (node (ref "P1") (pin "8") (pinfunction "8_8") (pintype "passive"))
      (node (ref "R201") (pin "3") (pinfunction "3_3") (pintype "passive"))
    )
    (net (code "85") (name "/PWM_W_L") (class "Default")
      (node (ref "B1") (pin "8") (pinfunction "4Y_8") (pintype "passive"))
      (node (ref "P1") (pin "7") (pinfunction "7_7") (pintype "passive"))
      (node (ref "R201") (pin "2") (pinfunction "2_2") (pintype "passive"))
    )
    (net (code "86") (name "/SPI1_LATCH") (class "Default")
      (node (ref "JX2") (pin "121") (pinfunction "SPI1_~{LATCH}_121") (pintype "output"))
    )
    (net (code "87") (name "/SPI1_MISO") (class "Default")
      (node (ref "JX2") (pin "120") (pinfunction "SPI1_MISO_120") (pintype "input+no_connect"))
    )
    (net (code "88") (name "/SPI1_MOSI") (class "Default")
      (node (ref "JX2") (pin "116") (pinfunction "SPI1_MOSI_116") (pintype "output"))
    )
    (net (code "89") (name "/SPI1_SCLK") (class "Default")
      (node (ref "JX2") (pin "119") (pinfunction "SPI1_SCLK_119") (pintype "output"))
    )
    (net (code "90") (name "/SPI1_nCS") (class "Default")
      (node (ref "JX2") (pin "117") (pinfunction "SPI1-~{CS}_117") (pintype "output"))
    )
    (net (code "91") (name "/SPI1_nRST") (class "Default")
      (node (ref "JX2") (pin "115") (pinfunction "SPI1_~{RST}_115") (pintype "output"))
    )
    (net (code "92") (name "/USER18") (class "Default")
      (node (ref "P11") (pin "1") (pinfunction "1_1") (pintype "passive"))
      (node (ref "R47") (pin "3") (pinfunction "3_3") (pintype "passive"))
    )
    (net (code "93") (name "/USER19") (class "Default")
      (node (ref "P11") (pin "2") (pinfunction "2_2") (pintype "passive"))
      (node (ref "R47") (pin "4") (pinfunction "4_4") (pintype "passive"))
    )
    (net (code "94") (name "/USER20") (class "Default")
      (node (ref "P11") (pin "3") (pinfunction "3_3") (pintype "passive"))
      (node (ref "R49") (pin "1") (pinfunction "1_1") (pintype "passive"))
    )
    (net (code "95") (name "/USER21") (class "Default")
      (node (ref "P11") (pin "4") (pinfunction "4_4") (pintype "passive"))
      (node (ref "R49") (pin "2") (pinfunction "2_2") (pintype "passive"))
    )
    (net (code "96") (name "/USER22") (class "Default")
      (node (ref "P11") (pin "5") (pinfunction "5_5") (pintype "passive"))
      (node (ref "R49") (pin "3") (pinfunction "3_3") (pintype "passive"))
    )
    (net (code "97") (name "/USER23") (class "Default")
      (node (ref "P11") (pin "6") (pinfunction "6_6") (pintype "passive"))
      (node (ref "R49") (pin "4") (pinfunction "4_4") (pintype "passive"))
    )
    (net (code "98") (name "/USER24") (class "Default")
      (node (ref "P11") (pin "7") (pinfunction "7_7") (pintype "passive"))
      (node (ref "R51") (pin "1") (pinfunction "1_1") (pintype "passive"))
    )
    (net (code "99") (name "/USER25") (class "Default")
      (node (ref "P11") (pin "8") (pinfunction "8_8") (pintype "passive"))
      (node (ref "R51") (pin "2") (pinfunction "2_2") (pintype "passive"))
    )
    (net (code "100") (name "/USER26") (class "Default")
      (node (ref "P11") (pin "9") (pinfunction "9_9") (pintype "passive"))
      (node (ref "R51") (pin "3") (pinfunction "3_3") (pintype "passive"))
    )
    (net (code "101") (name "/USER27") (class "Default")
      (node (ref "P15") (pin "1") (pinfunction "1_1") (pintype "passive"))
      (node (ref "R51") (pin "4") (pinfunction "4_4") (pintype "passive"))
    )
    (net (code "102") (name "/USER28") (class "Default")
      (node (ref "P15") (pin "2") (pinfunction "2_2") (pintype "passive"))
      (node (ref "R53") (pin "1") (pinfunction "1_1") (pintype "passive"))
    )
    (net (code "103") (name "/USER29") (class "Default")
      (node (ref "P15") (pin "3") (pinfunction "3_3") (pintype "passive"))
      (node (ref "R53") (pin "2") (pinfunction "2_2") (pintype "passive"))
    )
    (net (code "104") (name "/USER30") (class "Default")
      (node (ref "P15") (pin "4") (pinfunction "4_4") (pintype "passive"))
      (node (ref "R53") (pin "3") (pinfunction "3_3") (pintype "passive"))
    )
    (net (code "105") (name "/USER31") (class "Default")
      (node (ref "P15") (pin "5") (pinfunction "5_5") (pintype "passive"))
      (node (ref "R53") (pin "4") (pinfunction "4_4") (pintype "passive"))
    )
    (net (code "106") (name "/USER32") (class "Default")
      (node (ref "P15") (pin "6") (pinfunction "6_6") (pintype "passive"))
      (node (ref "R42") (pin "4") (pinfunction "4_4") (pintype "passive"))
    )
    (net (code "107") (name "/USER33") (class "Default")
      (node (ref "P15") (pin "7") (pinfunction "7_7") (pintype "passive"))
      (node (ref "R42") (pin "3") (pinfunction "3_3") (pintype "passive"))
    )
    (net (code "108") (name "/USER34") (class "Default")
      (node (ref "P15") (pin "8") (pinfunction "8_8") (pintype "passive"))
      (node (ref "R42") (pin "2") (pinfunction "2_2") (pintype "passive"))
    )
    (net (code "109") (name "/USER35") (class "Default")
      (node (ref "P15") (pin "9") (pinfunction "9_9") (pintype "passive"))
      (node (ref "R42") (pin "1") (pinfunction "1_1") (pintype "passive"))
    )
    (net (code "110") (name "/USR0") (class "Default")
      (node (ref "JX2") (pin "34") (pinfunction "USR0_34") (pintype "bidirectional"))
      (node (ref "R46") (pin "5") (pinfunction "5_5") (pintype "passive"))
    )
    (net (code "111") (name "/USR1") (class "Default")
      (node (ref "JX2") (pin "35") (pinfunction "USR1_35") (pintype "bidirectional"))
      (node (ref "R46") (pin "6") (pinfunction "6_6") (pintype "passive"))
    )
    (net (code "112") (name "/USR2") (class "Default")
      (node (ref "JX2") (pin "36") (pinfunction "USR2_36") (pintype "bidirectional"))
      (node (ref "R46") (pin "7") (pinfunction "7_7") (pintype "passive"))
    )
    (net (code "113") (name "/USR3") (class "Default")
      (node (ref "JX2") (pin "37") (pinfunction "USR3_37") (pintype "bidirectional"))
      (node (ref "R46") (pin "8") (pinfunction "8_8") (pintype "passive"))
    )
    (net (code "114") (name "/USR4") (class "Default")
      (node (ref "JX2") (pin "39") (pinfunction "USR4_39") (pintype "bidirectional"))
      (node (ref "R48") (pin "5") (pinfunction "5_5") (pintype "passive"))
    )
    (net (code "115") (name "/USR5") (class "Default")
      (node (ref "JX2") (pin "40") (pinfunction "USR5_40") (pintype "bidirectional"))
      (node (ref "R48") (pin "6") (pinfunction "6_6") (pintype "passive"))
    )
    (net (code "116") (name "/USR6") (class "Default")
      (node (ref "JX2") (pin "41") (pinfunction "USR6_41") (pintype "bidirectional"))
      (node (ref "R48") (pin "7") (pinfunction "7_7") (pintype "passive"))
    )
    (net (code "117") (name "/USR7") (class "Default")
      (node (ref "JX2") (pin "42") (pinfunction "USR7_42") (pintype "bidirectional"))
      (node (ref "R48") (pin "8") (pinfunction "8_8") (pintype "passive"))
    )
    (net (code "118") (name "/USR18") (class "Default")
      (node (ref "JX2") (pin "145") (pinfunction "USR18_145") (pintype "bidirectional"))
      (node (ref "R47") (pin "6") (pinfunction "6_6") (pintype "passive"))
    )
    (net (code "119") (name "/USR19") (class "Default")
      (node (ref "JX2") (pin "144") (pinfunction "USR19_144") (pintype "bidirectional"))
      (node (ref "R47") (pin "5") (pinfunction "5_5") (pintype "passive"))
    )
    (net (code "120") (name "/USR20") (class "Default")
      (node (ref "JX2") (pin "142") (pinfunction "USR20_142") (pintype "bidirectional"))
      (node (ref "R49") (pin "8") (pinfunction "8_8") (pintype "passive"))
    )
    (net (code "121") (name "/USR21") (class "Default")
      (node (ref "JX2") (pin "141") (pinfunction "USR21_141") (pintype "bidirectional"))
      (node (ref "R49") (pin "7") (pinfunction "7_7") (pintype "passive"))
    )
    (net (code "122") (name "/USR22") (class "Default")
      (node (ref "JX2") (pin "140") (pinfunction "USR22_140") (pintype "bidirectional"))
      (node (ref "R49") (pin "6") (pinfunction "6_6") (pintype "passive"))
    )
    (net (code "123") (name "/USR23") (class "Default")
      (node (ref "JX2") (pin "139") (pinfunction "USR23_139") (pintype "bidirectional"))
      (node (ref "R49") (pin "5") (pinfunction "5_5") (pintype "passive"))
    )
    (net (code "124") (name "/USR24") (class "Default")
      (node (ref "JX2") (pin "137") (pinfunction "USR24_137") (pintype "bidirectional"))
      (node (ref "R51") (pin "8") (pinfunction "8_8") (pintype "passive"))
    )
    (net (code "125") (name "/USR25") (class "Default")
      (node (ref "JX2") (pin "136") (pinfunction "USR25_136") (pintype "bidirectional"))
      (node (ref "R51") (pin "7") (pinfunction "7_7") (pintype "passive"))
    )
    (net (code "126") (name "/USR26") (class "Default")
      (node (ref "JX2") (pin "135") (pinfunction "USR26_135") (pintype "bidirectional"))
      (node (ref "R51") (pin "6") (pinfunction "6_6") (pintype "passive"))
    )
    (net (code "127") (name "/USR27") (class "Default")
      (node (ref "JX2") (pin "134") (pinfunction "USR27_134") (pintype "bidirectional"))
      (node (ref "R51") (pin "5") (pinfunction "5_5") (pintype "passive"))
    )
    (net (code "128") (name "/USR28") (class "Default")
      (node (ref "JX2") (pin "132") (pinfunction "USR28_132") (pintype "bidirectional"))
      (node (ref "R53") (pin "8") (pinfunction "8_8") (pintype "passive"))
    )
    (net (code "129") (name "/USR29") (class "Default")
      (node (ref "JX2") (pin "131") (pinfunction "USR29_131") (pintype "bidirectional"))
      (node (ref "R53") (pin "7") (pinfunction "7_7") (pintype "passive"))
    )
    (net (code "130") (name "/USR30") (class "Default")
      (node (ref "JX2") (pin "130") (pinfunction "USR30_130") (pintype "bidirectional"))
      (node (ref "R53") (pin "6") (pinfunction "6_6") (pintype "passive"))
    )
    (net (code "131") (name "/USR31") (class "Default")
      (node (ref "JX2") (pin "129") (pinfunction "USR31_129") (pintype "bidirectional"))
      (node (ref "R53") (pin "5") (pinfunction "5_5") (pintype "passive"))
    )
    (net (code "132") (name "/USR32") (class "Default")
      (node (ref "JX2") (pin "153") (pinfunction "USR32_153") (pintype "bidirectional"))
      (node (ref "R42") (pin "5") (pinfunction "5_5") (pintype "passive"))
    )
    (net (code "133") (name "/USR33") (class "Default")
      (node (ref "JX2") (pin "152") (pinfunction "USR33_152") (pintype "bidirectional"))
      (node (ref "R42") (pin "6") (pinfunction "6_6") (pintype "passive"))
    )
    (net (code "134") (name "/USR34") (class "Default")
      (node (ref "JX2") (pin "150") (pinfunction "USR34_150") (pintype "bidirectional"))
      (node (ref "R42") (pin "7") (pinfunction "7_7") (pintype "passive"))
    )
    (net (code "135") (name "/USR35") (class "Default")
      (node (ref "JX2") (pin "149") (pinfunction "USR35_149") (pintype "bidirectional"))
      (node (ref "R42") (pin "8") (pinfunction "8_8") (pintype "passive"))
    )
    (net (code "136") (name "/nFLT_IN") (class "Default")
      (node (ref "P13") (pin "1") (pinfunction "1_1") (pintype "passive"))
      (node (ref "R44") (pin "2") (pinfunction "2_2") (pintype "passive"))
    )
    (net (code "137") (name "/nFLT_OUT") (class "Default")
      (node (ref "P12") (pin "2") (pinfunction "2_2") (pintype "passive"))
      (node (ref "R43") (pin "2") (pinfunction "2_2") (pintype "passive"))
    )
    (net (code "139") (name "3V3") (class "Default")
      (node (ref "B1") (pin "14") (pinfunction "VCC_14") (pintype "power_in"))
      (node (ref "C78") (pin "2") (pinfunction "2_2") (pintype "passive"))
      (node (ref "C89") (pin "2") (pinfunction "2_2") (pintype "passive"))
      (node (ref "D4") (pin "K") (pinfunction "K_K") (pintype "passive"))
      (node (ref "P1") (pin "29") (pinfunction "29_29") (pintype "passive"))
      (node (ref "P12") (pin "1") (pinfunction "1_1") (pintype "passive"))
      (node (ref "R200") (pin "5") (pinfunction "5_5") (pintype "passive"))
      (node (ref "R200") (pin "6") (pinfunction "6_6") (pintype "passive"))
      (node (ref "R200") (pin "7") (pinfunction "7_7") (pintype "passive"))
      (node (ref "R200") (pin "8") (pinfunction "8_8") (pintype "passive"))
      (node (ref "R201") (pin "5") (pinfunction "5_5") (pintype "passive"))
      (node (ref "R201") (pin "6") (pinfunction "6_6") (pintype "passive"))
      (node (ref "R201") (pin "7") (pinfunction "7_7") (pintype "passive"))
      (node (ref "R201") (pin "8") (pinfunction "8_8") (pintype "passive"))
      (node (ref "R41") (pin "1") (pinfunction "1_1") (pintype "passive"))
    )
    (net (code "140") (name "GND") (class "Default")
      (node (ref "B1") (pin "7") (pinfunction "GND_7") (pintype "passive"))
      (node (ref "C78") (pin "1") (pinfunction "1_1") (pintype "passive"))
      (node (ref "C84") (pin "1") (pinfunction "1_1") (pintype "passive"))
      (node (ref "C89") (pin "1") (pinfunction "1_1") (pintype "passive"))
      (node (ref "JX2") (pin "1") (pinfunction "GND_1") (pintype "power_in"))
      (node (ref "JX2") (pin "104") (pinfunction "GND_104") (pintype "power_in"))
      (node (ref "JX2") (pin "109") (pinfunction "GND_109") (pintype "power_in"))
      (node (ref "JX2") (pin "11") (pinfunction "GND_11") (pintype "power_in"))
      (node (ref "JX2") (pin "114") (pinfunction "GND_114") (pintype "power_in"))
      (node (ref "JX2") (pin "118") (pinfunction "GND_118") (pintype "power_in"))
      (node (ref "JX2") (pin "12") (pinfunction "GND_12") (pintype "power_in"))
      (node (ref "JX2") (pin "122") (pinfunction "GND_122") (pintype "power_in"))
      (node (ref "JX2") (pin "128") (pinfunction "GND_128") (pintype "power_in"))
      (node (ref "JX2") (pin "133") (pinfunction "GND_133") (pintype "power_in"))
      (node (ref "JX2") (pin "138") (pinfunction "GND_138") (pintype "power_in"))
      (node (ref "JX2") (pin "143") (pinfunction "GND_143") (pintype "power_in"))
      (node (ref "JX2") (pin "148") (pinfunction "GND_148") (pintype "power_in"))
      (node (ref "JX2") (pin "151") (pinfunction "GND_151") (pintype "power_in"))
      (node (ref "JX2") (pin "154") (pinfunction "GND_154") (pintype "power_in"))
      (node (ref "JX2") (pin "159") (pinfunction "GND_159") (pintype "power_in"))
      (node (ref "JX2") (pin "164") (pinfunction "GND_164") (pintype "power_in"))
      (node (ref "JX2") (pin "169") (pinfunction "GND_169") (pintype "power_in"))
      (node (ref "JX2") (pin "17") (pinfunction "GND_17") (pintype "power_in"))
      (node (ref "JX2") (pin "174") (pinfunction "GND_174") (pintype "power_in"))
      (node (ref "JX2") (pin "175") (pinfunction "CARRIER_ID2_175") (pintype "passive"))
      (node (ref "JX2") (pin "176") (pinfunction "CARRIER_ID1_176") (pintype "passive"))
      (node (ref "JX2") (pin "177") (pinfunction "CARRIER_ID0_177") (pintype "passive"))
      (node (ref "JX2") (pin "178") (pinfunction "GND_178") (pintype "power_in"))
      (node (ref "JX2") (pin "179") (pinfunction "GND_179") (pintype "power_in"))
      (node (ref "JX2") (pin "180") (pinfunction "GND_180") (pintype "power_in"))
      (node (ref "JX2") (pin "2") (pinfunction "GND_2") (pintype "power_in"))
      (node (ref "JX2") (pin "22") (pinfunction "GND_22") (pintype "power_in"))
      (node (ref "JX2") (pin "27") (pinfunction "GND_27") (pintype "power_in"))
      (node (ref "JX2") (pin "3") (pinfunction "GND_3") (pintype "power_in"))
      (node (ref "JX2") (pin "30") (pinfunction "GND_30") (pintype "power_in"))
      (node (ref "JX2") (pin "33") (pinfunction "GND_33") (pintype "power_in"))
      (node (ref "JX2") (pin "38") (pinfunction "GND_38") (pintype "power_in"))
      (node (ref "JX2") (pin "4") (pinfunction "GND_4") (pintype "power_in"))
      (node (ref "JX2") (pin "43") (pinfunction "GND_43") (pintype "power_in"))
      (node (ref "JX2") (pin "48") (pinfunction "GND_48") (pintype "power_in"))
      (node (ref "JX2") (pin "53") (pinfunction "GND_53") (pintype "power_in"))
      (node (ref "JX2") (pin "59") (pinfunction "GND_59") (pintype "power_in"))
      (node (ref "JX2") (pin "63") (pinfunction "GND_63") (pintype "power_in"))
      (node (ref "JX2") (pin "67") (pinfunction "GND_67") (pintype "power_in"))
      (node (ref "JX2") (pin "7") (pinfunction "GND_7") (pintype "power_in"))
      (node (ref "JX2") (pin "72") (pinfunction "GND_72") (pintype "power_in"))
      (node (ref "JX2") (pin "77") (pinfunction "GND_77") (pintype "power_in"))
      (node (ref "JX2") (pin "8") (pinfunction "GND_8") (pintype "power_in"))
      (node (ref "JX2") (pin "82") (pinfunction "GND_82") (pintype "power_in"))
      (node (ref "JX2") (pin "87") (pinfunction "GND_87") (pintype "power_in"))
      (node (ref "JX2") (pin "88") (pinfunction "GND_88") (pintype "power_in"))
      (node (ref "JX2") (pin "89") (pinfunction "GND_89") (pintype "power_in"))
      (node (ref "JX2") (pin "90") (pinfunction "GND_90") (pintype "power_in"))
      (node (ref "JX2") (pin "91") (pinfunction "GND_91") (pintype "power_in"))
      (node (ref "JX2") (pin "92") (pinfunction "GND_92") (pintype "power_in"))
      (node (ref "JX2") (pin "93") (pinfunction "GND_93") (pintype "power_in"))
      (node (ref "JX2") (pin "94") (pinfunction "GND_94") (pintype "power_in"))
      (node (ref "JX2") (pin "99") (pinfunction "GND_99") (pintype "power_in"))
      (node (ref "P1") (pin "12") (pinfunction "12_12") (pintype "passive"))
      (node (ref "P1") (pin "30") (pinfunction "30_30") (pintype "passive"))
      (node (ref "P11") (pin "10") (pinfunction "10_10") (pintype "passive"))
      (node (ref "P13") (pin "2") (pinfunction "2_2") (pintype "passive"))
      (node (ref "P15") (pin "10") (pinfunction "10_10") (pintype "passive"))
      (node (ref "P17") (pin "1") (pinfunction "1_1") (pintype "passive"))
      (node (ref "P17") (pin "10") (pinfunction "10_10") (pintype "passive"))
      (node (ref "P18") (pin "1") (pinfunction "1_1") (pintype "passive"))
      (node (ref "P18") (pin "10") (pinfunction "10_10") (pintype "passive"))
      (node (ref "P2") (pin "5") (pinfunction "5_5") (pintype "passive"))
      (node (ref "P3") (pin "5") (pinfunction "5_5") (pintype "passive"))
      (node (ref "R54") (pin "5") (pinfunction "5_5") (pintype "passive"))
      (node (ref "R54") (pin "6") (pinfunction "6_6") (pintype "passive"))
      (node (ref "R54") (pin "7") (pinfunction "7_7") (pintype "passive"))
      (node (ref "R54") (pin "8") (pinfunction "8_8") (pintype "passive"))
      (node (ref "R55") (pin "5") (pinfunction "5_5") (pintype "passive"))
      (node (ref "R55") (pin "6") (pinfunction "6_6") (pintype "passive"))
      (node (ref "R55") (pin "7") (pinfunction "7_7") (pintype "passive"))
      (node (ref "R55") (pin "8") (pinfunction "8_8") (pintype "passive"))
      (node (ref "R56") (pin "5") (pinfunction "5_5") (pintype "passive"))
      (node (ref "R56") (pin "6") (pinfunction "6_6") (pintype "passive"))
      (node (ref "R56") (pin "7") (pinfunction "7_7") (pintype "passive"))
      (node (ref "R56") (pin "8") (pinfunction "8_8") (pintype "passive"))
      (node (ref "R57") (pin "5") (pinfunction "5_5") (pintype "passive"))
      (node (ref "R57") (pin "6") (pinfunction "6_6") (pintype "passive"))
      (node (ref "R57") (pin "7") (pinfunction "7_7") (pintype "passive"))
      (node (ref "R57") (pin "8") (pinfunction "8_8") (pintype "passive"))
      (node (ref "R66") (pin "5") (pinfunction "5_5") (pintype "passive"))
      (node (ref "R66") (pin "6") (pinfunction "6_6") (pintype "passive"))
      (node (ref "R66") (pin "7") (pinfunction "7_7") (pintype "passive"))
      (node (ref "R66") (pin "8") (pinfunction "8_8") (pintype "passive"))
      (node (ref "R67") (pin "5") (pinfunction "5_5") (pintype "passive"))
      (node (ref "R67") (pin "6") (pinfunction "6_6") (pintype "passive"))
      (node (ref "R67") (pin "7") (pinfunction "7_7") (pintype "passive"))
      (node (ref "R67") (pin "8") (pinfunction "8_8") (pintype "passive"))
      (node (ref "R68") (pin "5") (pinfunction "5_5") (pintype "passive"))
      (node (ref "R68") (pin "6") (pinfunction "6_6") (pintype "passive"))
      (node (ref "R68") (pin "7") (pinfunction "7_7") (pintype "passive"))
      (node (ref "R68") (pin "8") (pinfunction "8_8") (pintype "passive"))
      (node (ref "R69") (pin "5") (pinfunction "5_5") (pintype "passive"))
      (node (ref "R69") (pin "6") (pinfunction "6_6") (pintype "passive"))
      (node (ref "R69") (pin "7") (pinfunction "7_7") (pintype "passive"))
      (node (ref "R69") (pin "8") (pinfunction "8_8") (pintype "passive"))
      (node (ref "R84") (pin "1") (pinfunction "1_1") (pintype "passive"))
    )
    (net (code "141") (name "Net-(P21-Pad2)") (class "Default")
      (node (ref "P21") (pin "2") (pinfunction "2_2") (pintype "passive"))
      (node (ref "R84") (pin "2") (pinfunction "2_2") (pintype "passive"))
    )
    (net (code "142") (name "unconnected-(JX2-GTX_RX3_N-Pad9)") (class "Default")
      (node (ref "JX2") (pin "9") (pinfunction "GTX_RX3_N_9") (pintype "input+no_connect"))
    )
    (net (code "143") (name "unconnected-(JX2-GTX_RX3_P-Pad10)") (class "Default")
      (node (ref "JX2") (pin "10") (pinfunction "GTX_RX3_P_10") (pintype "input+no_connect"))
    )
    (net (code "144") (name "unconnected-(JX2-GTX_TX3_N-Pad5)") (class "Default")
      (node (ref "JX2") (pin "5") (pinfunction "GTX_TX3_N_5") (pintype "output+no_connect"))
    )
    (net (code "145") (name "unconnected-(JX2-GTX_TX3_P-Pad6)") (class "Default")
      (node (ref "JX2") (pin "6") (pinfunction "GTX_TX3_P_6") (pintype "output+no_connect"))
    )
    (net (code "146") (name "unconnected-(JX2-JTAG1_TCK-Pad56)") (class "Default")
      (node (ref "JX2") (pin "56") (pinfunction "JTAG1_TCK_56") (pintype "passive+no_connect"))
    )
    (net (code "147") (name "unconnected-(JX2-JTAG1_TDI-Pad58)") (class "Default")
      (node (ref "JX2") (pin "58") (pinfunction "JTAG1_TDI_58") (pintype "passive+no_connect"))
    )
    (net (code "148") (name "unconnected-(JX2-JTAG1_TDO-Pad57)") (class "Default")
      (node (ref "JX2") (pin "57") (pinfunction "JTAG1_TDO_57") (pintype "passive+no_connect"))
    )
    (net (code "149") (name "unconnected-(JX2-JTAG1_TMS-Pad55)") (class "Default")
      (node (ref "JX2") (pin "55") (pinfunction "JTAG1_TMS_55") (pintype "passive+no_connect"))
    )
    (net (code "150") (name "unconnected-(JX2-JTAG1_VREF-Pad54)") (class "Default")
      (node (ref "JX2") (pin "54") (pinfunction "JTAG1_VREF_54") (pintype "passive+no_connect"))
    )
    (net (code "151") (name "unconnected-(JX2-NC-Pad123)") (class "Default")
      (node (ref "JX2") (pin "123") (pinfunction "NC_123") (pintype "passive+no_connect"))
    )
    (net (code "152") (name "unconnected-(JX2-NC-Pad124)") (class "Default")
      (node (ref "JX2") (pin "124") (pinfunction "NC_124") (pintype "passive+no_connect"))
    )
    (net (code "153") (name "unconnected-(JX2-NC-Pad125)") (class "Default")
      (node (ref "JX2") (pin "125") (pinfunction "NC_125") (pintype "passive+no_connect"))
    )
    (net (code "154") (name "unconnected-(JX2-NC-Pad126)") (class "Default")
      (node (ref "JX2") (pin "126") (pinfunction "NC_126") (pintype "passive+no_connect"))
    )
    (net (code "155") (name "unconnected-(JX2-NC-Pad127)") (class "Default")
      (node (ref "JX2") (pin "127") (pinfunction "NC_127") (pintype "passive+no_connect"))
    )
    (net (code "156") (name "unconnected-(JX2-SPI0_A0-Pad62)") (class "Default")
      (node (ref "JX2") (pin "62") (pinfunction "SPI0_A0_62") (pintype "output+no_connect"))
    )
    (net (code "157") (name "unconnected-(JX2-SPI0_A1-Pad65)") (class "Default")
      (node (ref "JX2") (pin "65") (pinfunction "SPI0_A1_65") (pintype "output+no_connect"))
    )
    (net (code "158") (name "unconnected-(JX2-SPI0_A2-Pad66)") (class "Default")
      (node (ref "JX2") (pin "66") (pinfunction "SPI0_A2_66") (pintype "output+no_connect"))
    )
    (net (code "159") (name "unconnected-(JX2-SPI0_MISO-Pad60)") (class "Default")
      (node (ref "JX2") (pin "60") (pinfunction "SPI0_MISO_60") (pintype "input+no_connect"))
    )
    (net (code "160") (name "unconnected-(JX2-SPI0_MOSI-Pad61)") (class "Default")
      (node (ref "JX2") (pin "61") (pinfunction "SPI0_MOSI_61") (pintype "output+no_connect"))
    )
    (net (code "161") (name "unconnected-(JX2-SPI0_SCLK-Pad64)") (class "Default")
      (node (ref "JX2") (pin "64") (pinfunction "SPI0_SCLK_64") (pintype "output+no_connect"))
    )
    (net (code "162") (name "unconnected-(JX2-USR8-Pad44)") (class "Default")
      (node (ref "JX2") (pin "44") (pinfunction "USR8_44") (pintype "bidirectional+no_connect"))
    )
    (net (code "163") (name "unconnected-(JX2-USR9-Pad45)") (class "Default")
      (node (ref "JX2") (pin "45") (pinfunction "USR9_45") (pintype "bidirectional+no_connect"))
    )
    (net (code "164") (name "unconnected-(JX2-USR10-Pad46)") (class "Default")
      (node (ref "JX2") (pin "46") (pinfunction "USR10_46") (pintype "bidirectional+no_connect"))
    )
    (net (code "165") (name "unconnected-(JX2-USR11-Pad47)") (class "Default")
      (node (ref "JX2") (pin "47") (pinfunction "USR11_47") (pintype "bidirectional+no_connect"))
    )
    (net (code "166") (name "unconnected-(JX2-USR12-Pad49)") (class "Default")
      (node (ref "JX2") (pin "49") (pinfunction "USR12_49") (pintype "bidirectional+no_connect"))
    )
    (net (code "167") (name "unconnected-(JX2-USR13-Pad50)") (class "Default")
      (node (ref "JX2") (pin "50") (pinfunction "USR13_50") (pintype "bidirectional+no_connect"))
    )
    (net (code "168") (name "unconnected-(JX2-USR14-Pad51)") (class "Default")
      (node (ref "JX2") (pin "51") (pinfunction "USR14_51") (pintype "bidirectional+no_connect"))
    )
    (net (code "169") (name "unconnected-(JX2-USR15-Pad52)") (class "Default")
      (node (ref "JX2") (pin "52") (pinfunction "USR15_52") (pintype "bidirectional+no_connect"))
    )
    (net (code "170") (name "unconnected-(JX2-USR16-Pad147)") (class "Default")
      (node (ref "JX2") (pin "147") (pinfunction "USR16_147") (pintype "bidirectional+no_connect"))
    )
    (net (code "171") (name "unconnected-(JX2-USR17-Pad146)") (class "Default")
      (node (ref "JX2") (pin "146") (pinfunction "USR17_146") (pintype "bidirectional+no_connect"))
    )
    (net (code "172") (name "unconnected-(P1-Pad15)") (class "Default")
      (node (ref "P1") (pin "15") (pinfunction "15_15") (pintype "passive"))
    )
    (net (code "173") (name "unconnected-(P1-Pad16)") (class "Default")
      (node (ref "P1") (pin "16") (pinfunction "16_16") (pintype "passive"))
    )
    (net (code "174") (name "unconnected-(P1-Pad17)") (class "Default")
      (node (ref "P1") (pin "17") (pinfunction "17_17") (pintype "passive"))
    )
    (net (code "175") (name "unconnected-(P1-Pad20)") (class "Default")
      (node (ref "P1") (pin "20") (pinfunction "20_20") (pintype "passive"))
    )
    (net (code "176") (name "unconnected-(P1-Pad22)") (class "Default")
      (node (ref "P1") (pin "22") (pinfunction "22_22") (pintype "passive"))
    )
    (net (code "177") (name "unconnected-(P1-Pad23)") (class "Default")
      (node (ref "P1") (pin "23") (pinfunction "23_23") (pintype "passive"))
    )
    (net (code "178") (name "unconnected-(P1-Pad24)") (class "Default")
      (node (ref "P1") (pin "24") (pinfunction "24_24") (pintype "passive"))
    )
    (net (code "179") (name "unconnected-(P1-Pad25)") (class "Default")
      (node (ref "P1") (pin "25") (pinfunction "25_25") (pintype "passive"))
    )
    (net (code "180") (name "unconnected-(P1-Pad26)") (class "Default")
      (node (ref "P1") (pin "26") (pinfunction "26_26") (pintype "passive"))
    )
    (net (code "181") (name "unconnected-(P1-Pad27)") (class "Default")
      (node (ref "P1") (pin "27") (pinfunction "27_27") (pintype "passive"))
    )
    (net (code "182") (name "unconnected-(P1-Pad28)") (class "Default")
      (node (ref "P1") (pin "28") (pinfunction "28_28") (pintype "passive"))
    )
    (net (code "183") (name "unconnected-(P1-Pad31)") (class "Default")
      (node (ref "P1") (pin "31") (pinfunction "31_31") (pintype "passive"))
    )
    (net (code "184") (name "unconnected-(P1-Pad32)") (class "Default")
      (node (ref "P1") (pin "32") (pinfunction "32_32") (pintype "passive"))
    )
    (net (code "185") (name "unconnected-(P1-Pad33)") (class "Default")
      (node (ref "P1") (pin "33") (pinfunction "33_33") (pintype "passive"))
    )
    (net (code "186") (name "unconnected-(P1-Pad34)") (class "Default")
      (node (ref "P1") (pin "34") (pinfunction "34_34") (pintype "passive"))
    )
    (net (code "187") (name "unconnected-(P1-Pad35)") (class "Default")
      (node (ref "P1") (pin "35") (pinfunction "35_35") (pintype "passive"))
    )
    (net (code "188") (name "unconnected-(P1-Pad36)") (class "Default")
      (node (ref "P1") (pin "36") (pinfunction "36_36") (pintype "passive"))
    )
    (net (code "189") (name "unconnected-(P1-Pad37)") (class "Default")
      (node (ref "P1") (pin "37") (pinfunction "37_37") (pintype "passive"))
    )
    (net (code "190") (name "unconnected-(P1-Pad38)") (class "Default")
      (node (ref "P1") (pin "38") (pinfunction "38_38") (pintype "passive"))
    )
    (net (code "191") (name "unconnected-(P1-Pad39)") (class "Default")
      (node (ref "P1") (pin "39") (pinfunction "39_39") (pintype "passive"))
    )
    (net (code "192") (name "unconnected-(P1-Pad40)") (class "Default")
      (node (ref "P1") (pin "40") (pinfunction "40_40") (pintype "passive"))
    )
    (net (code "193") (name "unconnected-(P17-Pad2)") (class "Default")
      (node (ref "P17") (pin "2") (pinfunction "2_2") (pintype "passive+no_connect"))
    )
    (net (code "194") (name "unconnected-(R47-Pad1)") (class "Default")
      (node (ref "R47") (pin "1") (pinfunction "1_1") (pintype "passive+no_connect"))
    )
    (net (code "195") (name "unconnected-(R47-Pad2)") (class "Default")
      (node (ref "R47") (pin "2") (pinfunction "2_2") (pintype "passive+no_connect"))
    )
    (net (code "196") (name "unconnected-(R47-Pad7)") (class "Default")
      (node (ref "R47") (pin "7") (pinfunction "7_7") (pintype "passive+no_connect"))
    )
    (net (code "197") (name "unconnected-(R47-Pad8)") (class "Default")
      (node (ref "R47") (pin "8") (pinfunction "8_8") (pintype "passive+no_connect"))
    )
    (net (code "198") (name "unconnected-(R200-Pad1)") (class "Default")
      (node (ref "R200") (pin "1") (pinfunction "1_1") (pintype "passive+no_connect"))
    )
    (net (code "199") (name "unconnected-(R201-Pad1)") (class "Default")
      (node (ref "R201") (pin "1") (pinfunction "1_1") (pintype "passive+no_connect"))
    )
  )
)
